# ATMega328_Control_Board.net
KiCad netlist of a schematic drawn in Altium Designer
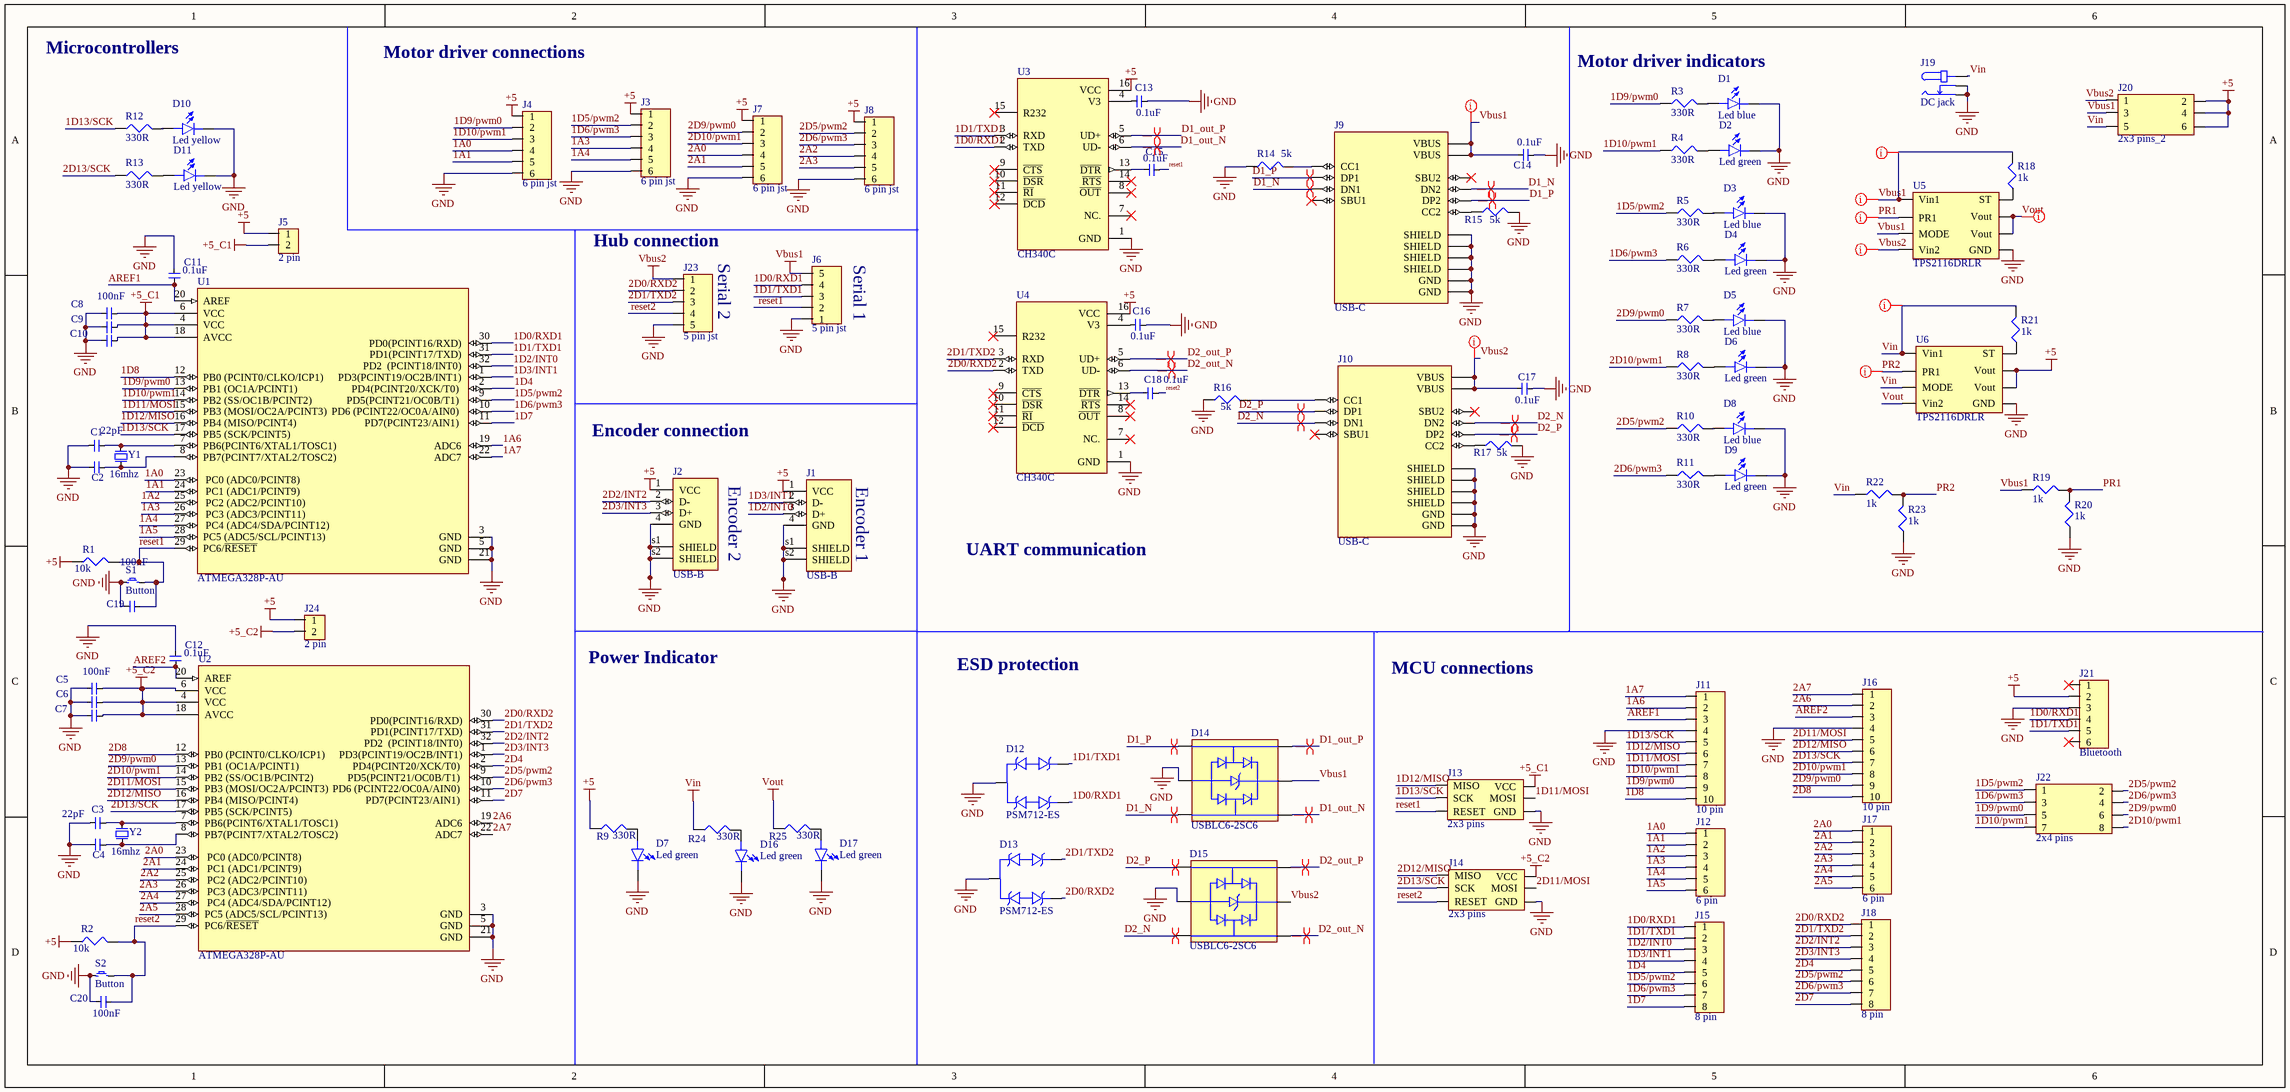
[diagram p0: ATMega328 Control Board.SchDoc]

(export (version "E")
  (design (tool "Eeschema 10.0.6"))
  (components
    (comp (ref "C1")
      (value "22pF")
      (footprint "0603 cap")
      (description "50V 22pF C0G ±5% 0603 Multilayer Ceramic Capacitors MLCC - SMD/SMT ROHS")
      (fields
        (field (name "MANUFACTURER") "PSA(Prosperity Dielectrics)")
        (field (name "MFR. PART #") "FN18N220J500PSG")
      )
      (libsource (lib "Schlib1") (part "22pF capacitor"))
    )
    (comp (ref "C2")
      (value "22pF")
      (footprint "0603 cap")
      (description "50V 22pF C0G ±5% 0603 Multilayer Ceramic Capacitors MLCC - SMD/SMT ROHS")
      (fields
        (field (name "MANUFACTURER") "PSA(Prosperity Dielectrics)")
        (field (name "MFR. PART #") "FN18N220J500PSG")
      )
      (libsource (lib "Schlib1") (part "22pF capacitor"))
    )
    (comp (ref "C3")
      (value "22pF")
      (footprint "0603 cap")
      (description "50V 22pF C0G ±5% 0603 Multilayer Ceramic Capacitors MLCC - SMD/SMT ROHS")
      (fields
        (field (name "MANUFACTURER") "PSA(Prosperity Dielectrics)")
        (field (name "MFR. PART #") "FN18N220J500PSG")
      )
      (libsource (lib "Schlib1") (part "22pF capacitor"))
    )
    (comp (ref "C4")
      (value "22pF")
      (footprint "0603 cap")
      (description "50V 22pF C0G ±5% 0603 Multilayer Ceramic Capacitors MLCC - SMD/SMT ROHS")
      (fields
        (field (name "MANUFACTURER") "PSA(Prosperity Dielectrics)")
        (field (name "MFR. PART #") "FN18N220J500PSG")
      )
      (libsource (lib "Schlib1") (part "22pF capacitor"))
    )
    (comp (ref "C5")
      (value "100nF")
      (footprint "0603 cap")
      (description "50V 100nF X7R ±10% 0603 Multilayer Ceramic Capacitors MLCC - SMD/SMT ROHS")
      (fields
        (field (name "MANUFACTURER") "PSA(Prosperity Dielectrics)")
        (field (name "MFR. PART #") "FN18X104K500PBG")
      )
      (libsource (lib "Schlib1") (part "100nF capacitor"))
    )
    (comp (ref "C6")
      (value "100nF")
      (footprint "0603 cap")
      (description "50V 100nF X7R ±10% 0603 Multilayer Ceramic Capacitors MLCC - SMD/SMT ROHS")
      (fields
        (field (name "MANUFACTURER") "PSA(Prosperity Dielectrics)")
        (field (name "MFR. PART #") "FN18X104K500PBG")
      )
      (libsource (lib "Schlib1") (part "100nF capacitor"))
    )
    (comp (ref "C7")
      (value "100nF")
      (footprint "0603 cap")
      (description "50V 100nF X7R ±10% 0603 Multilayer Ceramic Capacitors MLCC - SMD/SMT ROHS")
      (fields
        (field (name "MANUFACTURER") "PSA(Prosperity Dielectrics)")
        (field (name "MFR. PART #") "FN18X104K500PBG")
      )
      (libsource (lib "Schlib1") (part "100nF capacitor"))
    )
    (comp (ref "C8")
      (value "100nF")
      (footprint "0603 cap")
      (description "50V 100nF X7R ±10% 0603 Multilayer Ceramic Capacitors MLCC - SMD/SMT ROHS")
      (fields
        (field (name "MANUFACTURER") "PSA(Prosperity Dielectrics)")
        (field (name "MFR. PART #") "FN18X104K500PBG")
      )
      (libsource (lib "Schlib1") (part "100nF capacitor"))
    )
    (comp (ref "C9")
      (value "100nF")
      (footprint "0603 cap")
      (description "50V 100nF X7R ±10% 0603 Multilayer Ceramic Capacitors MLCC - SMD/SMT ROHS")
      (fields
        (field (name "MANUFACTURER") "PSA(Prosperity Dielectrics)")
        (field (name "MFR. PART #") "FN18X104K500PBG")
      )
      (libsource (lib "Schlib1") (part "100nF capacitor"))
    )
    (comp (ref "C10")
      (value "100nF")
      (footprint "0603 cap")
      (description "50V 100nF X7R ±10% 0603 Multilayer Ceramic Capacitors MLCC - SMD/SMT ROHS")
      (fields
        (field (name "MANUFACTURER") "PSA(Prosperity Dielectrics)")
        (field (name "MFR. PART #") "FN18X104K500PBG")
      )
      (libsource (lib "Schlib1") (part "100nF capacitor"))
    )
    (comp (ref "C11")
      (value "0.1uF")
      (footprint "0603 cap")
      (description "50V 100nF X7R ±10% 0603 Multilayer Ceramic Capacitors MLCC - SMD/SMT ROHS")
      (fields
        (field (name "MANUFACTURER") "PSA(Prosperity Dielectrics)")
        (field (name "MFR. PART #") "FN18X104K500PBG")
      )
      (libsource (lib "Schlib1") (part "100nF capacitor"))
    )
    (comp (ref "C12")
      (value "0.1uF")
      (footprint "0603 cap")
      (description "50V 100nF X7R ±10% 0603 Multilayer Ceramic Capacitors MLCC - SMD/SMT ROHS")
      (fields
        (field (name "MANUFACTURER") "PSA(Prosperity Dielectrics)")
        (field (name "MFR. PART #") "FN18X104K500PBG")
      )
      (libsource (lib "Schlib1") (part "100nF capacitor"))
    )
    (comp (ref "C13")
      (value "0.1uF")
      (footprint "0603 cap")
      (description "50V 100nF X7R ±10% 0603 Multilayer Ceramic Capacitors MLCC - SMD/SMT ROHS")
      (fields
        (field (name "MANUFACTURER") "PSA(Prosperity Dielectrics)")
        (field (name "MFR. PART #") "FN18X104K500PBG")
      )
      (libsource (lib "Schlib1") (part "100nF capacitor"))
    )
    (comp (ref "C14")
      (value "0.1uF")
      (footprint "0603 cap")
      (description "50V 100nF X7R ±10% 0603 Multilayer Ceramic Capacitors MLCC - SMD/SMT ROHS")
      (fields
        (field (name "MANUFACTURER") "PSA(Prosperity Dielectrics)")
        (field (name "MFR. PART #") "FN18X104K500PBG")
      )
      (libsource (lib "Schlib1") (part "100nF capacitor"))
    )
    (comp (ref "C15")
      (value "0.1uF")
      (footprint "0603 cap")
      (description "50V 100nF X7R ±10% 0603 Multilayer Ceramic Capacitors MLCC - SMD/SMT ROHS")
      (fields
        (field (name "MANUFACTURER") "PSA(Prosperity Dielectrics)")
        (field (name "MFR. PART #") "FN18X104K500PBG")
      )
      (libsource (lib "Schlib1") (part "100nF capacitor"))
    )
    (comp (ref "C16")
      (value "0.1uF")
      (footprint "0603 cap")
      (description "50V 100nF X7R ±10% 0603 Multilayer Ceramic Capacitors MLCC - SMD/SMT ROHS")
      (fields
        (field (name "MANUFACTURER") "PSA(Prosperity Dielectrics)")
        (field (name "MFR. PART #") "FN18X104K500PBG")
      )
      (libsource (lib "Schlib1") (part "100nF capacitor"))
    )
    (comp (ref "C17")
      (value "0.1uF")
      (footprint "0603 cap")
      (description "50V 100nF X7R ±10% 0603 Multilayer Ceramic Capacitors MLCC - SMD/SMT ROHS")
      (fields
        (field (name "MANUFACTURER") "PSA(Prosperity Dielectrics)")
        (field (name "MFR. PART #") "FN18X104K500PBG")
      )
      (libsource (lib "Schlib1") (part "100nF capacitor"))
    )
    (comp (ref "C18")
      (value "0.1uF")
      (footprint "0603 cap")
      (description "50V 100nF X7R ±10% 0603 Multilayer Ceramic Capacitors MLCC - SMD/SMT ROHS")
      (fields
        (field (name "MANUFACTURER") "PSA(Prosperity Dielectrics)")
        (field (name "MFR. PART #") "FN18X104K500PBG")
      )
      (libsource (lib "Schlib1") (part "100nF capacitor"))
    )
    (comp (ref "C19")
      (value "100nF")
      (footprint "0603 cap")
      (description "50V 100nF X7R ±10% 0603 Multilayer Ceramic Capacitors MLCC - SMD/SMT ROHS")
      (fields
        (field (name "MANUFACTURER") "PSA(Prosperity Dielectrics)")
        (field (name "MFR. PART #") "FN18X104K500PBG")
      )
      (libsource (lib "Schlib1") (part "100nF capacitor"))
    )
    (comp (ref "C20")
      (value "100nF")
      (footprint "0603 cap")
      (description "50V 100nF X7R ±10% 0603 Multilayer Ceramic Capacitors MLCC - SMD/SMT ROHS")
      (fields
        (field (name "MANUFACTURER") "PSA(Prosperity Dielectrics)")
        (field (name "MFR. PART #") "FN18X104K500PBG")
      )
      (libsource (lib "Schlib1") (part "100nF capacitor"))
    )
    (comp (ref "D1")
      (value "Led blue")
      (footprint "0805led")
      (description "Blue 0603 Light Emitting Diodes (LED) ROHS")
      (fields (field (name "MANUFACTURER") "Yongyu Photoelectric") (field (name "MFR. PART #") "SZYY0805B"))
      (libsource (lib "Schlib1") (part "Led blue"))
    )
    (comp (ref "D2")
      (value "Led green")
      (footprint "0805led")
      (description "Emerald 0805 Light Emitting Diodes (LED) ROHS")
      (fields (field (name "MANUFACTURER") "Yongyu Photoelectric") (field (name "MFR. PART #") "SZYY0805G"))
      (libsource (lib "Schlib1") (part "Led green"))
    )
    (comp (ref "D3")
      (value "Led blue")
      (footprint "0805led")
      (description "Blue 0603 Light Emitting Diodes (LED) ROHS")
      (fields (field (name "MANUFACTURER") "Yongyu Photoelectric") (field (name "MFR. PART #") "SZYY0805B"))
      (libsource (lib "Schlib1") (part "Led blue"))
    )
    (comp (ref "D4")
      (value "Led green")
      (footprint "0805led")
      (description "Emerald 0805 Light Emitting Diodes (LED) ROHS")
      (fields (field (name "MANUFACTURER") "Yongyu Photoelectric") (field (name "MFR. PART #") "SZYY0805G"))
      (libsource (lib "Schlib1") (part "Led green"))
    )
    (comp (ref "D5")
      (value "Led blue")
      (footprint "0805led")
      (description "Blue 0603 Light Emitting Diodes (LED) ROHS")
      (fields (field (name "MANUFACTURER") "Yongyu Photoelectric") (field (name "MFR. PART #") "SZYY0805B"))
      (libsource (lib "Schlib1") (part "Led blue"))
    )
    (comp (ref "D6")
      (value "Led green")
      (footprint "0805led")
      (description "Emerald 0805 Light Emitting Diodes (LED) ROHS")
      (fields (field (name "MANUFACTURER") "Yongyu Photoelectric") (field (name "MFR. PART #") "SZYY0805G"))
      (libsource (lib "Schlib1") (part "Led green"))
    )
    (comp (ref "D7")
      (value "Led green")
      (footprint "0805led")
      (description "Emerald 0805 Light Emitting Diodes (LED) ROHS")
      (fields (field (name "MANUFACTURER") "Yongyu Photoelectric") (field (name "MFR. PART #") "SZYY0805G"))
      (libsource (lib "Schlib1") (part "Led green"))
    )
    (comp (ref "D8")
      (value "Led blue")
      (footprint "0805led")
      (description "Blue 0603 Light Emitting Diodes (LED) ROHS")
      (fields (field (name "MANUFACTURER") "Yongyu Photoelectric") (field (name "MFR. PART #") "SZYY0805B"))
      (libsource (lib "Schlib1") (part "Led blue"))
    )
    (comp (ref "D9")
      (value "Led green")
      (footprint "0805led")
      (description "Emerald 0805 Light Emitting Diodes (LED) ROHS")
      (fields (field (name "MANUFACTURER") "Yongyu Photoelectric") (field (name "MFR. PART #") "SZYY0805G"))
      (libsource (lib "Schlib1") (part "Led green"))
    )
    (comp (ref "D10")
      (value "Led yellow")
      (footprint "0805led")
      (description "10mA 无色透明透镜 -40℃~+85℃ 584nm~594nm Yellow 120° 40mW 0805 Light Emitting Diodes (LED) ROHS")
      (fields (field (name "MANUFACTURER") "Yongyu Photoelectric") (field (name "MFR. PART #") "SZYY0805Y"))
      (libsource (lib "Schlib1") (part "Led yellow"))
    )
    (comp (ref "D11")
      (value "Led yellow")
      (footprint "0805led")
      (description "10mA 无色透明透镜 -40℃~+85℃ 584nm~594nm Yellow 120° 40mW 0805 Light Emitting Diodes (LED) ROHS")
      (fields (field (name "MANUFACTURER") "Yongyu Photoelectric") (field (name "MFR. PART #") "SZYY0805Y"))
      (libsource (lib "Schlib1") (part "Led yellow"))
    )
    (comp (ref "D12")
      (value "PSM712-ES")
      (footprint "sop23")
      (description "17A 350W Bi-Directional SOT-23 Electrostatic and Surge Protection (TVS/ESD) ROHS")
      (fields (field (name "MANUFACTURER") "ElecSuper") (field (name "LCSC PART #") "C5180294"))
      (libsource (lib "Schlib1") (part "PSM712-ES"))
    )
    (comp (ref "D13")
      (value "PSM712-ES")
      (footprint "sop23")
      (description "17A 350W Bi-Directional SOT-23 Electrostatic and Surge Protection (TVS/ESD) ROHS")
      (fields (field (name "MANUFACTURER") "ElecSuper") (field (name "LCSC PART #") "C5180294"))
      (libsource (lib "Schlib1") (part "PSM712-ES"))
    )
    (comp (ref "D14")
      (value "USBLC6-2SC6")
      (footprint "SOP23-6l")
      (description "5A 17V 6V Unidirectional 5.25V SOT-23-6 Electrostatic and Surge Protection (TVS/ESD) ROHS")
      (fields (field (name "MANUFACTURER") "STMicroelectronics") (field (name "LCSC PART #") "C7519"))
      (libsource (lib "Schlib1") (part "USBLC6-2SC6"))
    )
    (comp (ref "D15")
      (value "USBLC6-2SC6")
      (footprint "SOP23-6l")
      (description "5A 17V 6V Unidirectional 5.25V SOT-23-6 Electrostatic and Surge Protection (TVS/ESD) ROHS")
      (fields (field (name "MANUFACTURER") "STMicroelectronics") (field (name "LCSC PART #") "C7519"))
      (libsource (lib "Schlib1") (part "USBLC6-2SC6"))
    )
    (comp (ref "D16")
      (value "Led green")
      (footprint "0805led")
      (description "Emerald 0805 Light Emitting Diodes (LED) ROHS")
      (fields (field (name "MANUFACTURER") "Yongyu Photoelectric") (field (name "MFR. PART #") "SZYY0805G"))
      (libsource (lib "Schlib1") (part "Led green"))
    )
    (comp (ref "D17")
      (value "Led green")
      (footprint "0805led")
      (description "Emerald 0805 Light Emitting Diodes (LED) ROHS")
      (fields (field (name "MANUFACTURER") "Yongyu Photoelectric") (field (name "MFR. PART #") "SZYY0805G"))
      (libsource (lib "Schlib1") (part "Led green"))
    )
    (comp (ref "J1")
      (value "USB-B")
      (footprint "USB")
      (description "USB 2.0 1 4P Female Type-B Plugin USB Connectors ROHS\r\n ROHS")
      (fields
        (field (name "MANUFACTURER") "Jing Extension of the Electronic Co.")
        (field (name "MFR. PART #") "921-111A1010D10200")
      )
      (libsource (lib "Schlib1") (part "USB-B"))
    )
    (comp (ref "J2")
      (value "USB-B")
      (footprint "USB")
      (description "USB 2.0 1 4P Female Type-B Plugin USB Connectors ROHS\r\n ROHS")
      (fields
        (field (name "MANUFACTURER") "Jing Extension of the Electronic Co.")
        (field (name "MFR. PART #") "921-111A1010D10200")
      )
      (libsource (lib "Schlib1") (part "USB-B"))
    )
    (comp (ref "J3")
      (value "6 pin jst")
      (footprint "6 jst")
      (description "1x6P 6P XH 1 2.5mm 6 Plugin,P=2.5mm Wire To Board Connector ROHS")
      (fields (field (name "MANUFACTURER") "BOOMELE") (field (name "MFR. PART #") "XH-6A"))
      (libsource (lib "Schlib1") (part "6 pin jst"))
    )
    (comp (ref "J4")
      (value "6 pin jst")
      (footprint "6 jst")
      (description "1x6P 6P XH 1 2.5mm 6 Plugin,P=2.5mm Wire To Board Connector ROHS")
      (fields (field (name "MANUFACTURER") "BOOMELE") (field (name "MFR. PART #") "XH-6A"))
      (libsource (lib "Schlib1") (part "6 pin jst"))
    )
    (comp (ref "J5")
      (value "2 pin")
      (footprint "2 pin header")
      (fields
        (field (name "MANUFACTURER") "XUNPU")
        (field (name "MFR. PART #") "PH2.54-01-02PZD")
        (field (name "LCSC PART #") "C7501580")
      )
      (libsource (lib "Schlib1") (part "2 pin"))
    )
    (comp (ref "J6")
      (value "5 pin jst")
      (footprint "5 jst")
      (description "1x5P 5P XH 1 2.5mm 6 Plugin,P=2.5mm Wire To Board Connector ROHS")
      (fields (field (name "MANUFACTURER") "BOOMELE") (field (name "MFR. PART #") "XH-6A"))
      (libsource (lib "") (part "5 pin jst_1"))
    )
    (comp (ref "J7")
      (value "6 pin jst")
      (footprint "6 jst")
      (description "1x6P 6P XH 1 2.5mm 6 Plugin,P=2.5mm Wire To Board Connector ROHS")
      (fields (field (name "MANUFACTURER") "BOOMELE") (field (name "MFR. PART #") "XH-6A"))
      (libsource (lib "Schlib1") (part "6 pin jst"))
    )
    (comp (ref "J8")
      (value "6 pin jst")
      (footprint "6 jst")
      (description "1x6P 6P XH 1 2.5mm 6 Plugin,P=2.5mm Wire To Board Connector ROHS")
      (fields (field (name "MANUFACTURER") "BOOMELE") (field (name "MFR. PART #") "XH-6A"))
      (libsource (lib "Schlib1") (part "6 pin jst"))
    )
    (comp (ref "J9")
      (value "USB-C")
      (footprint "USB-C")
      (description "5A 1 16P Female Type-C SMD USB Connectors ROHS")
      (fields
        (field (name "MANUFACTURER") "Korean Hroparts Elec")
        (field (name "MFR. PART #") "TYPE-C-31-M-12")
      )
      (libsource (lib "Schlib1") (part "USB-C"))
    )
    (comp (ref "J10")
      (value "USB-C")
      (footprint "USB-C")
      (description "5A 1 16P Female Type-C SMD USB Connectors ROHS")
      (fields
        (field (name "MANUFACTURER") "Korean Hroparts Elec")
        (field (name "MFR. PART #") "TYPE-C-31-M-12")
      )
      (libsource (lib "Schlib1") (part "USB-C"))
    )
    (comp (ref "J11")
      (value "10 pin")
      (footprint "10 pin header")
      (fields
        (field (name "MANUFACTURER") "Shenzhen Kinghelm Elec")
        (field (name "MFR. PART #") "KH-2.54FH-1X10P-H8.5")
        (field (name "LCSC PART #") "C2905418")
      )
      (libsource (lib "Schlib1") (part "10 pin"))
    )
    (comp (ref "J12")
      (value "6 pin")
      (footprint "6 pin header")
      (description "2.54mm Plugin 6P Straight 1x6P Plugin,P=2.54mm Female Headers ROHS")
      (fields (field (name "MANUFACTURER") "BOOMELE") (field (name "MFR. PART #") "2.54-1*6P"))
      (libsource (lib "Schlib1") (part "6 pin"))
    )
    (comp (ref "J13")
      (value "2x3 pins")
      (footprint "2x3 pins")
      (description "Straight 2.54mm 6mm 6P 3mm 2.54mm 双排 2x3P Plugin,P=2.54mm Pin Headers ROHS")
      (fields (field (name "MANUFACTURER") "HanElectricity") (field (name "MFR. PART #") "2541WV-2x03P"))
      (libsource (lib "Schlib1") (part "2x3 pins"))
    )
    (comp (ref "J14")
      (value "2x3 pins")
      (footprint "2x3 pins")
      (description "Straight 2.54mm 6mm 6P 3mm 2.54mm 双排 2x3P Plugin,P=2.54mm Pin Headers ROHS")
      (fields (field (name "MANUFACTURER") "HanElectricity") (field (name "MFR. PART #") "2541WV-2x03P"))
      (libsource (lib "Schlib1") (part "2x3 pins"))
    )
    (comp (ref "J15")
      (value "8 pin")
      (footprint "8 pin heade")
      (description "2.54mm Plugin 8P Straight 1x8P Plugin,P=2.54mm Female Headers ROHS")
      (fields (field (name "MANUFACTURER") "BOOMELE") (field (name "MFR. PART #") "2.54-1*8P"))
      (libsource (lib "Schlib1") (part "8 pin"))
    )
    (comp (ref "J16")
      (value "10 pin")
      (footprint "10 pin header")
      (fields
        (field (name "MANUFACTURER") "Shenzhen Kinghelm Elec")
        (field (name "MFR. PART #") "KH-2.54FH-1X10P-H8.5")
        (field (name "LCSC PART #") "C2905418")
      )
      (libsource (lib "Schlib1") (part "10 pin"))
    )
    (comp (ref "J17")
      (value "6 pin")
      (footprint "6 pin header")
      (description "2.54mm Plugin 6P Straight 1x6P Plugin,P=2.54mm Female Headers ROHS")
      (fields (field (name "MANUFACTURER") "BOOMELE") (field (name "MFR. PART #") "2.54-1*6P"))
      (libsource (lib "Schlib1") (part "6 pin"))
    )
    (comp (ref "J18")
      (value "8 pin")
      (footprint "8 pin heade")
      (description "2.54mm Plugin 8P Straight 1x8P Plugin,P=2.54mm Female Headers ROHS")
      (fields (field (name "MANUFACTURER") "BOOMELE") (field (name "MFR. PART #") "2.54-1*8P"))
      (libsource (lib "Schlib1") (part "8 pin"))
    )
    (comp (ref "J19")
      (value "DC jack")
      (footprint "DC jack")
      (fields
        (field (name "MANUFACTURER") "XKB Connection")
        (field (name "MFR. PART #") "DC-005-2.5A-2.0")
        (field (name "LCSC PART #") "C319099")
      )
      (libsource (lib "Schlib1") (part "DC jack"))
    )
    (comp (ref "J20")
      (value "2x3 pins_2")
      (footprint "2x3 pins")
      (description "Straight 2.54mm 6mm 6P 3mm 2.54mm 双排 2x3P Plugin,P=2.54mm Pin Headers ROHS")
      (fields (field (name "MANUFACTURER") "HanElectricity") (field (name "MFR. PART #") "2541WV-2x03P"))
      (libsource (lib "Schlib1") (part "2x3 pins_2"))
    )
    (comp (ref "J21")
      (value "Bluetooth")
      (footprint "6 pin header")
      (description "2.54mm Plugin 6P Straight 1x6P Plugin,P=2.54mm Female Headers ROHS")
      (fields (field (name "MANUFACTURER") "BOOMELE") (field (name "MFR. PART #") "2.54-1*6P"))
      (libsource (lib "Schlib1") (part "6 pin"))
    )
    (comp (ref "J22")
      (value "2x4 pins")
      (footprint "2x4 pins")
      (fields
        (field (name "MANUFACTURER") "Liansheng")
        (field (name "MFR. PART #") "PH-00179")
        (field (name "LCSC PART #") "C2829882")
      )
      (libsource (lib "Schlib1") (part "2x4 pins"))
    )
    (comp (ref "J23")
      (value "5 pin jst")
      (footprint "5 jst")
      (description "1x5P 5P XH 1 2.5mm 6 Plugin,P=2.5mm Wire To Board Connector ROHS")
      (fields (field (name "MANUFACTURER") "BOOMELE") (field (name "MFR. PART #") "XH-6A"))
      (libsource (lib "Schlib1") (part "5 pin jst"))
    )
    (comp (ref "J24")
      (value "2 pin")
      (footprint "2 pin header")
      (fields
        (field (name "MANUFACTURER") "XUNPU")
        (field (name "MFR. PART #") "PH2.54-01-02PZD")
        (field (name "LCSC PART #") "C7501580")
      )
      (libsource (lib "Schlib1") (part "2 pin"))
    )
    (comp (ref "R1")
      (value "10k")
      (footprint "0603 cap")
      (description "100mW Thick Film Resistors 75V ±100ppm/℃ ±1% 10kΩ 0603 Chip Resistor - Surface Mount ROHS")
      (fields
        (field (name "MANUFACTURER") "UNI-ROYAL(Uniroyal Elec)")
        (field (name "MFR. PART #") "0603WAF1002T5E")
      )
      (libsource (lib "Schlib1") (part "10k resistor"))
    )
    (comp (ref "R2")
      (value "10k")
      (footprint "0603 cap")
      (description "100mW Thick Film Resistors 75V ±100ppm/℃ ±1% 10kΩ 0603 Chip Resistor - Surface Mount ROHS")
      (fields
        (field (name "MANUFACTURER") "UNI-ROYAL(Uniroyal Elec)")
        (field (name "MFR. PART #") "0603WAF1002T5E")
      )
      (libsource (lib "Schlib1") (part "10k resistor"))
    )
    (comp (ref "R3")
      (value "330R")
      (footprint "0603 cap")
      (description "100mW Thick Film Resistors 75V ±100ppm/℃ ±1% 330Ω 0603 Chip Resistor - Surface Mount ROHS")
      (fields
        (field (name "MANUFACTURER") "UNI-ROYAL(Uniroyal Elec)")
        (field (name "MFR. PART #") "0603WAF3300T5E")
      )
      (libsource (lib "Schlib1") (part "330R"))
    )
    (comp (ref "R4")
      (value "330R")
      (footprint "0603 cap")
      (description "100mW Thick Film Resistors 75V ±100ppm/℃ ±1% 330Ω 0603 Chip Resistor - Surface Mount ROHS")
      (fields
        (field (name "MANUFACTURER") "UNI-ROYAL(Uniroyal Elec)")
        (field (name "MFR. PART #") "0603WAF3300T5E")
      )
      (libsource (lib "Schlib1") (part "330R"))
    )
    (comp (ref "R5")
      (value "330R")
      (footprint "0603 cap")
      (description "100mW Thick Film Resistors 75V ±100ppm/℃ ±1% 330Ω 0603 Chip Resistor - Surface Mount ROHS")
      (fields
        (field (name "MANUFACTURER") "UNI-ROYAL(Uniroyal Elec)")
        (field (name "MFR. PART #") "0603WAF3300T5E")
      )
      (libsource (lib "Schlib1") (part "330R"))
    )
    (comp (ref "R6")
      (value "330R")
      (footprint "0603 cap")
      (description "100mW Thick Film Resistors 75V ±100ppm/℃ ±1% 330Ω 0603 Chip Resistor - Surface Mount ROHS")
      (fields
        (field (name "MANUFACTURER") "UNI-ROYAL(Uniroyal Elec)")
        (field (name "MFR. PART #") "0603WAF3300T5E")
      )
      (libsource (lib "Schlib1") (part "330R"))
    )
    (comp (ref "R7")
      (value "330R")
      (footprint "0603 cap")
      (description "100mW Thick Film Resistors 75V ±100ppm/℃ ±1% 330Ω 0603 Chip Resistor - Surface Mount ROHS")
      (fields
        (field (name "MANUFACTURER") "UNI-ROYAL(Uniroyal Elec)")
        (field (name "MFR. PART #") "0603WAF3300T5E")
      )
      (libsource (lib "Schlib1") (part "330R"))
    )
    (comp (ref "R8")
      (value "330R")
      (footprint "0603 cap")
      (description "100mW Thick Film Resistors 75V ±100ppm/℃ ±1% 330Ω 0603 Chip Resistor - Surface Mount ROHS")
      (fields
        (field (name "MANUFACTURER") "UNI-ROYAL(Uniroyal Elec)")
        (field (name "MFR. PART #") "0603WAF3300T5E")
      )
      (libsource (lib "Schlib1") (part "330R"))
    )
    (comp (ref "R9")
      (value "330R")
      (footprint "0603 cap")
      (description "100mW Thick Film Resistors 75V ±100ppm/℃ ±1% 330Ω 0603 Chip Resistor - Surface Mount ROHS")
      (fields
        (field (name "MANUFACTURER") "UNI-ROYAL(Uniroyal Elec)")
        (field (name "MFR. PART #") "0603WAF3300T5E")
      )
      (libsource (lib "Schlib1") (part "330R"))
    )
    (comp (ref "R10")
      (value "330R")
      (footprint "0603 cap")
      (description "100mW Thick Film Resistors 75V ±100ppm/℃ ±1% 330Ω 0603 Chip Resistor - Surface Mount ROHS")
      (fields
        (field (name "MANUFACTURER") "UNI-ROYAL(Uniroyal Elec)")
        (field (name "MFR. PART #") "0603WAF3300T5E")
      )
      (libsource (lib "Schlib1") (part "330R"))
    )
    (comp (ref "R11")
      (value "330R")
      (footprint "0603 cap")
      (description "100mW Thick Film Resistors 75V ±100ppm/℃ ±1% 330Ω 0603 Chip Resistor - Surface Mount ROHS")
      (fields
        (field (name "MANUFACTURER") "UNI-ROYAL(Uniroyal Elec)")
        (field (name "MFR. PART #") "0603WAF3300T5E")
      )
      (libsource (lib "Schlib1") (part "330R"))
    )
    (comp (ref "R12")
      (value "330R")
      (footprint "0603 cap")
      (description "100mW Thick Film Resistors 75V ±100ppm/℃ ±1% 330Ω 0603 Chip Resistor - Surface Mount ROHS")
      (fields
        (field (name "MANUFACTURER") "UNI-ROYAL(Uniroyal Elec)")
        (field (name "MFR. PART #") "0603WAF3300T5E")
      )
      (libsource (lib "Schlib1") (part "330R"))
    )
    (comp (ref "R13")
      (value "330R")
      (footprint "0603 cap")
      (description "100mW Thick Film Resistors 75V ±100ppm/℃ ±1% 330Ω 0603 Chip Resistor - Surface Mount ROHS")
      (fields
        (field (name "MANUFACTURER") "UNI-ROYAL(Uniroyal Elec)")
        (field (name "MFR. PART #") "0603WAF3300T5E")
      )
      (libsource (lib "Schlib1") (part "330R"))
    )
    (comp (ref "R14")
      (value "5k")
      (footprint "0603 cap")
      (description "100mW Thick Film Resistors 75V ±100ppm/℃ ±1% 330Ω 0603 Chip Resistor - Surface Mount ROHS")
      (fields
        (field (name "MANUFACTURER") "UNI-ROYAL(Uniroyal Elec)")
        (field (name "MFR. PART #") "0603WAF5101T5E")
      )
      (libsource (lib "Schlib1") (part "5k"))
    )
    (comp (ref "R15")
      (value "5k")
      (footprint "0603 cap")
      (description "100mW Thick Film Resistors 75V ±100ppm/℃ ±1% 330Ω 0603 Chip Resistor - Surface Mount ROHS")
      (fields
        (field (name "MANUFACTURER") "UNI-ROYAL(Uniroyal Elec)")
        (field (name "MFR. PART #") "0603WAF5101T5E")
      )
      (libsource (lib "Schlib1") (part "5k"))
    )
    (comp (ref "R16")
      (value "5k")
      (footprint "0603 cap")
      (description "100mW Thick Film Resistors 75V ±100ppm/℃ ±1% 330Ω 0603 Chip Resistor - Surface Mount ROHS")
      (fields
        (field (name "MANUFACTURER") "UNI-ROYAL(Uniroyal Elec)")
        (field (name "MFR. PART #") "0603WAF5101T5E")
      )
      (libsource (lib "Schlib1") (part "5k"))
    )
    (comp (ref "R17")
      (value "5k")
      (footprint "0603 cap")
      (description "100mW Thick Film Resistors 75V ±100ppm/℃ ±1% 330Ω 0603 Chip Resistor - Surface Mount ROHS")
      (fields
        (field (name "MANUFACTURER") "UNI-ROYAL(Uniroyal Elec)")
        (field (name "MFR. PART #") "0603WAF5101T5E")
      )
      (libsource (lib "Schlib1") (part "5k"))
    )
    (comp (ref "R18")
      (value "1k")
      (footprint "0603 cap")
      (description "100mW Thick Film Resistors 75V ±100ppm/℃ ±1% 1kΩ 0603 Chip Resistor - Surface Mount ROHS")
      (fields
        (field (name "MANUFACTURER") "UNI-ROYAL(Uniroyal Elec)")
        (field (name "MFR. PART #") "0603WAF1001T5E")
      )
      (libsource (lib "Schlib1") (part "1k resistor"))
    )
    (comp (ref "R19")
      (value "1k")
      (footprint "0603 cap")
      (description "100mW Thick Film Resistors 75V ±100ppm/℃ ±1% 1kΩ 0603 Chip Resistor - Surface Mount ROHS")
      (fields
        (field (name "MANUFACTURER") "UNI-ROYAL(Uniroyal Elec)")
        (field (name "MFR. PART #") "0603WAF1001T5E")
      )
      (libsource (lib "Schlib1") (part "1k resistor"))
    )
    (comp (ref "R20")
      (value "1k")
      (footprint "0603 cap")
      (description "100mW Thick Film Resistors 75V ±100ppm/℃ ±1% 1kΩ 0603 Chip Resistor - Surface Mount ROHS")
      (fields
        (field (name "MANUFACTURER") "UNI-ROYAL(Uniroyal Elec)")
        (field (name "MFR. PART #") "0603WAF1001T5E")
      )
      (libsource (lib "Schlib1") (part "1k resistor"))
    )
    (comp (ref "R21")
      (value "1k")
      (footprint "0603 cap")
      (description "100mW Thick Film Resistors 75V ±100ppm/℃ ±1% 1kΩ 0603 Chip Resistor - Surface Mount ROHS")
      (fields
        (field (name "MANUFACTURER") "UNI-ROYAL(Uniroyal Elec)")
        (field (name "MFR. PART #") "0603WAF1001T5E")
      )
      (libsource (lib "Schlib1") (part "1k resistor"))
    )
    (comp (ref "R22")
      (value "1k")
      (footprint "0603 cap")
      (description "100mW Thick Film Resistors 75V ±100ppm/℃ ±1% 1kΩ 0603 Chip Resistor - Surface Mount ROHS")
      (fields
        (field (name "MANUFACTURER") "UNI-ROYAL(Uniroyal Elec)")
        (field (name "MFR. PART #") "0603WAF1001T5E")
      )
      (libsource (lib "Schlib1") (part "1k resistor"))
    )
    (comp (ref "R23")
      (value "1k")
      (footprint "0603 cap")
      (description "100mW Thick Film Resistors 75V ±100ppm/℃ ±1% 1kΩ 0603 Chip Resistor - Surface Mount ROHS")
      (fields
        (field (name "MANUFACTURER") "UNI-ROYAL(Uniroyal Elec)")
        (field (name "MFR. PART #") "0603WAF1001T5E")
      )
      (libsource (lib "Schlib1") (part "1k resistor"))
    )
    (comp (ref "R24")
      (value "330R")
      (footprint "0603 cap")
      (description "100mW Thick Film Resistors 75V ±100ppm/℃ ±1% 330Ω 0603 Chip Resistor - Surface Mount ROHS")
      (fields
        (field (name "MANUFACTURER") "UNI-ROYAL(Uniroyal Elec)")
        (field (name "MFR. PART #") "0603WAF3300T5E")
      )
      (libsource (lib "Schlib1") (part "330R"))
    )
    (comp (ref "R25")
      (value "330R")
      (footprint "0603 cap")
      (description "100mW Thick Film Resistors 75V ±100ppm/℃ ±1% 330Ω 0603 Chip Resistor - Surface Mount ROHS")
      (fields
        (field (name "MANUFACTURER") "UNI-ROYAL(Uniroyal Elec)")
        (field (name "MFR. PART #") "0603WAF3300T5E")
      )
      (libsource (lib "Schlib1") (part "330R"))
    )
    (comp (ref "S1")
      (value "Button")
      (footprint "button")
      (fields
        (field (name "MANUFACTURER") "USAKRO")
        (field (name "MFR. PART #") "UK-B0240-R-250")
        (field (name "LCSC PART #") "C556660")
      )
      (libsource (lib "Schlib1") (part "tactile button"))
    )
    (comp (ref "S2")
      (value "Button")
      (footprint "button")
      (fields
        (field (name "MANUFACTURER") "USAKRO")
        (field (name "MFR. PART #") "UK-B0240-R-250")
        (field (name "LCSC PART #") "C556660")
      )
      (libsource (lib "Schlib1") (part "tactile button"))
    )
    (comp (ref "U1")
      (value "ATMEGA328P-AU")
      (footprint "Quad32")
      (description "32KB 2KB FLASH 23 1.8V~5.5V AVR 20MHz TQFP-32(7x7) Microcontroller Units (MCUs/MPUs/SOCs) ROHS")
      (fields (field (name "MANUFACTURER") "Microchip Tech") (field (name "LCSC PART #") "C14877"))
      (libsource (lib "Schlib1") (part "ATMEGA328P-AU"))
    )
    (comp (ref "U2")
      (value "ATMEGA328P-AU")
      (footprint "Quad32")
      (description "32KB 2KB FLASH 23 1.8V~5.5V AVR 20MHz TQFP-32(7x7) Microcontroller Units (MCUs/MPUs/SOCs) ROHS")
      (fields (field (name "MANUFACTURER") "Microchip Tech") (field (name "LCSC PART #") "C14877"))
      (libsource (lib "Schlib1") (part "ATMEGA328P-AU"))
    )
    (comp (ref "U3")
      (value "CH340C")
      (footprint "sop 16")
      (description "2Mbps Transceiver USB 2.0 SOP-16 USB ICs ROHS")
      (fields (field (name "MANUFACTURER") "WCH") (field (name "LCSC PART #") "C84681"))
      (libsource (lib "Schlib1") (part "CH340C"))
    )
    (comp (ref "U4")
      (value "CH340C")
      (footprint "sop 16")
      (description "2Mbps Transceiver USB 2.0 SOP-16 USB ICs ROHS")
      (fields (field (name "MANUFACTURER") "WCH") (field (name "LCSC PART #") "C84681"))
      (libsource (lib "Schlib1") (part "CH340C"))
    )
    (comp (ref "U5")
      (value "TPS2116DRLR")
      (footprint "SOP8")
      (description "1.6V~5.5V 42mΩ 2.5A 1 SOT-583 Power Distribution Switches ROHS")
      (fields (field (name "MANUFACTURER") "Texas Instruments") (field (name "LCSC PART #") "C3235557"))
      (libsource (lib "Schlib1") (part "TPS2116DRLR"))
    )
    (comp (ref "U6")
      (value "TPS2116DRLR")
      (footprint "SOP8")
      (description "1.6V~5.5V 42mΩ 2.5A 1 SOT-583 Power Distribution Switches ROHS")
      (fields (field (name "MANUFACTURER") "Texas Instruments") (field (name "LCSC PART #") "C3235557"))
      (libsource (lib "Schlib1") (part "TPS2116DRLR"))
    )
    (comp (ref "Y1")
      (value "16mhz")
      (footprint "crystal")
      (description "16MHz 16pF ±20ppm ±20ppm HC-49S-SMD Crystals ROHS")
      (fields (field (name "MANUFACTURER") "KYX") (field (name "MFR. PART #") "KBD160001620"))
      (libsource (lib "Schlib1") (part "Crystal 16mhz"))
    )
    (comp (ref "Y2")
      (value "16mhz")
      (footprint "crystal")
      (description "16MHz 16pF ±20ppm ±20ppm HC-49S-SMD Crystals ROHS")
      (fields (field (name "MANUFACTURER") "KYX") (field (name "MFR. PART #") "KBD160001620"))
      (libsource (lib "Schlib1") (part "Crystal 16mhz"))
    )
  )
  (nets
    (net (code "1") (name "+5") (class "Default")
      (node (ref "J1") (pin "1") (pinfunction "VCC_1") (pintype "power_in"))
      (node (ref "J2") (pin "1") (pinfunction "VCC_1") (pintype "power_in"))
      (node (ref "J20") (pin "2") (pinfunction "2_2") (pintype "passive"))
      (node (ref "J20") (pin "4") (pinfunction "4_4") (pintype "passive"))
      (node (ref "J20") (pin "6") (pinfunction "6_6") (pintype "passive"))
      (node (ref "J21") (pin "2") (pinfunction "2_2") (pintype "passive"))
      (node (ref "J24") (pin "1") (pinfunction "1_1") (pintype "passive"))
      (node (ref "J3") (pin "1") (pinfunction "1_1") (pintype "passive"))
      (node (ref "J4") (pin "1") (pinfunction "1_1") (pintype "passive"))
      (node (ref "J5") (pin "1") (pinfunction "1_1") (pintype "passive"))
      (node (ref "J7") (pin "1") (pinfunction "1_1") (pintype "passive"))
      (node (ref "J8") (pin "1") (pinfunction "1_1") (pintype "passive"))
      (node (ref "R1") (pin "1") (pinfunction "1_1") (pintype "passive"))
      (node (ref "R2") (pin "1") (pinfunction "1_1") (pintype "passive"))
      (node (ref "R9") (pin "1") (pinfunction "1_1") (pintype "passive"))
      (node (ref "U3") (pin "16") (pinfunction "VCC_16") (pintype "power_in"))
      (node (ref "U4") (pin "16") (pinfunction "VCC_16") (pintype "power_in"))
      (node (ref "U6") (pin "2") (pinfunction "Vout_2") (pintype "passive"))
      (node (ref "U6") (pin "7") (pinfunction "Vout_7") (pintype "passive"))
    )
    (net (code "2") (name "+5_C1") (class "Default")
      (node (ref "C10") (pin "2") (pinfunction "2_2") (pintype "passive"))
      (node (ref "C8") (pin "2") (pinfunction "2_2") (pintype "passive"))
      (node (ref "C9") (pin "2") (pinfunction "2_2") (pintype "passive"))
      (node (ref "J13") (pin "2") (pinfunction "VCC_2") (pintype "passive"))
      (node (ref "J5") (pin "2") (pinfunction "2_2") (pintype "passive"))
      (node (ref "U1") (pin "18") (pinfunction "AVCC_18") (pintype "power_in"))
      (node (ref "U1") (pin "4") (pinfunction "VCC_4") (pintype "power_in"))
      (node (ref "U1") (pin "6") (pinfunction "VCC_6") (pintype "power_in"))
    )
    (net (code "3") (name "+5_C2") (class "Default")
      (node (ref "C5") (pin "2") (pinfunction "2_2") (pintype "passive"))
      (node (ref "C6") (pin "2") (pinfunction "2_2") (pintype "passive"))
      (node (ref "C7") (pin "2") (pinfunction "2_2") (pintype "passive"))
      (node (ref "J14") (pin "2") (pinfunction "VCC_2") (pintype "passive"))
      (node (ref "J24") (pin "2") (pinfunction "2_2") (pintype "passive"))
      (node (ref "U2") (pin "18") (pinfunction "AVCC_18") (pintype "power_in"))
      (node (ref "U2") (pin "4") (pinfunction "VCC_4") (pintype "power_in"))
      (node (ref "U2") (pin "6") (pinfunction "VCC_6") (pintype "power_in"))
    )
    (net (code "4") (name "/1A0") (class "Default")
      (node (ref "J12") (pin "1") (pinfunction "1_1") (pintype "passive"))
      (node (ref "J4") (pin "4") (pinfunction "4_4") (pintype "passive"))
      (node (ref "U1") (pin "23") (pinfunction "_PC0_(ADC0/PCINT8)_23") (pintype "bidirectional"))
    )
    (net (code "5") (name "/1A1") (class "Default")
      (node (ref "J12") (pin "2") (pinfunction "2_2") (pintype "passive"))
      (node (ref "J4") (pin "5") (pinfunction "5_5") (pintype "passive"))
      (node (ref "U1") (pin "24") (pinfunction "_PC1_(ADC1/PCINT9)_24") (pintype "bidirectional"))
    )
    (net (code "6") (name "/1A2") (class "Default")
      (node (ref "J12") (pin "3") (pinfunction "3_3") (pintype "passive"))
      (node (ref "U1") (pin "25") (pinfunction "_PC2_(ADC2/PCINT10)_25") (pintype "bidirectional"))
    )
    (net (code "7") (name "/1A3") (class "Default")
      (node (ref "J12") (pin "4") (pinfunction "4_4") (pintype "passive"))
      (node (ref "J3") (pin "4") (pinfunction "4_4") (pintype "passive"))
      (node (ref "U1") (pin "26") (pinfunction "_PC3_(ADC3/PCINT11)_26") (pintype "bidirectional"))
    )
    (net (code "8") (name "/1A4") (class "Default")
      (node (ref "J12") (pin "5") (pinfunction "5_5") (pintype "passive"))
      (node (ref "J3") (pin "5") (pinfunction "5_5") (pintype "passive"))
      (node (ref "U1") (pin "27") (pinfunction "_PC4_(ADC4/SDA/PCINT12)_27") (pintype "bidirectional"))
    )
    (net (code "9") (name "/1A5") (class "Default")
      (node (ref "J12") (pin "6") (pinfunction "6_6") (pintype "passive"))
      (node (ref "U1") (pin "28") (pinfunction "PC5_(ADC5/SCL/PCINT13)_28") (pintype "bidirectional"))
    )
    (net (code "10") (name "/1A6") (class "Default")
      (node (ref "J11") (pin "2") (pinfunction "2_2") (pintype "passive"))
      (node (ref "U1") (pin "19") (pinfunction "ADC6_19") (pintype "bidirectional"))
    )
    (net (code "11") (name "/1A7") (class "Default")
      (node (ref "J11") (pin "1") (pinfunction "1_1") (pintype "passive"))
      (node (ref "U1") (pin "22") (pinfunction "ADC7_22") (pintype "bidirectional"))
    )
    (net (code "12") (name "/1D0{slash}RXD1") (class "Default")
      (node (ref "D12") (pin "1") (pinfunction "1_1") (pintype "passive"))
      (node (ref "J15") (pin "1") (pinfunction "1_1") (pintype "passive"))
      (node (ref "J21") (pin "4") (pinfunction "4_4") (pintype "passive"))
      (node (ref "J6") (pin "4") (pinfunction "4_4") (pintype "passive"))
      (node (ref "U1") (pin "30") (pinfunction "PD0(PCINT16/RXD)_30") (pintype "bidirectional"))
      (node (ref "U3") (pin "2") (pinfunction "TXD_2") (pintype "bidirectional"))
    )
    (net (code "13") (name "/1D1{slash}TXD1") (class "Default")
      (node (ref "D12") (pin "2") (pinfunction "2_2") (pintype "passive"))
      (node (ref "J15") (pin "2") (pinfunction "2_2") (pintype "passive"))
      (node (ref "J21") (pin "5") (pinfunction "5_5") (pintype "passive"))
      (node (ref "J6") (pin "3") (pinfunction "3_3") (pintype "passive"))
      (node (ref "U1") (pin "31") (pinfunction "PD1(PCINT17/TXD)_31") (pintype "bidirectional"))
      (node (ref "U3") (pin "3") (pinfunction "RXD_3") (pintype "bidirectional"))
    )
    (net (code "14") (name "/1D2{slash}INT0") (class "Default")
      (node (ref "J1") (pin "3") (pinfunction "D+_3") (pintype "bidirectional"))
      (node (ref "J15") (pin "3") (pinfunction "3_3") (pintype "passive"))
      (node (ref "U1") (pin "32") (pinfunction "PD2__(PCINT18/INT0)_32") (pintype "bidirectional"))
    )
    (net (code "15") (name "/1D3{slash}INT1") (class "Default")
      (node (ref "J1") (pin "2") (pinfunction "D-_2") (pintype "bidirectional"))
      (node (ref "J15") (pin "4") (pinfunction "4_4") (pintype "passive"))
      (node (ref "U1") (pin "1") (pinfunction "PD3(PCINT19/OC2B/INT1)_1") (pintype "bidirectional"))
    )
    (net (code "16") (name "/1D4") (class "Default")
      (node (ref "J15") (pin "5") (pinfunction "5_5") (pintype "passive"))
      (node (ref "U1") (pin "2") (pinfunction "PD4(PCINT20/XCK/T0)_2") (pintype "bidirectional"))
    )
    (net (code "17") (name "/1D5{slash}pwm2") (class "Default")
      (node (ref "J15") (pin "6") (pinfunction "6_6") (pintype "passive"))
      (node (ref "J22") (pin "1") (pinfunction "1_1") (pintype "passive"))
      (node (ref "J3") (pin "2") (pinfunction "2_2") (pintype "passive"))
      (node (ref "R5") (pin "1") (pinfunction "1_1") (pintype "passive"))
      (node (ref "U1") (pin "9") (pinfunction "PD5(PCINT21/OC0B/T1)_9") (pintype "bidirectional"))
    )
    (net (code "18") (name "/1D6{slash}pwm3") (class "Default")
      (node (ref "J15") (pin "7") (pinfunction "7_7") (pintype "passive"))
      (node (ref "J22") (pin "3") (pinfunction "3_3") (pintype "passive"))
      (node (ref "J3") (pin "3") (pinfunction "3_3") (pintype "passive"))
      (node (ref "R6") (pin "1") (pinfunction "1_1") (pintype "passive"))
      (node (ref "U1") (pin "10") (pinfunction "PD6_(PCINT22/OC0A/AIN0)_10") (pintype "bidirectional"))
    )
    (net (code "19") (name "/1D7") (class "Default")
      (node (ref "J15") (pin "8") (pinfunction "8_8") (pintype "passive"))
      (node (ref "U1") (pin "11") (pinfunction "PD7(PCINT23/AIN1)_11") (pintype "bidirectional"))
    )
    (net (code "20") (name "/1D8") (class "Default")
      (node (ref "J11") (pin "10") (pinfunction "10_10") (pintype "passive"))
      (node (ref "U1") (pin "12") (pinfunction "PB0_(PCINT0/CLKO/ICP1)_12") (pintype "bidirectional"))
    )
    (net (code "21") (name "/1D9{slash}pwm0") (class "Default")
      (node (ref "J11") (pin "9") (pinfunction "9_9") (pintype "passive"))
      (node (ref "J22") (pin "5") (pinfunction "5_5") (pintype "passive"))
      (node (ref "J4") (pin "2") (pinfunction "2_2") (pintype "passive"))
      (node (ref "R3") (pin "1") (pinfunction "1_1") (pintype "passive"))
      (node (ref "U1") (pin "13") (pinfunction "PB1_(OC1A/PCINT1)_13") (pintype "bidirectional"))
    )
    (net (code "22") (name "/1D10{slash}pwm1") (class "Default")
      (node (ref "J11") (pin "8") (pinfunction "8_8") (pintype "passive"))
      (node (ref "J22") (pin "7") (pinfunction "7_7") (pintype "passive"))
      (node (ref "J4") (pin "3") (pinfunction "3_3") (pintype "passive"))
      (node (ref "R4") (pin "1") (pinfunction "1_1") (pintype "passive"))
      (node (ref "U1") (pin "14") (pinfunction "PB2_(SS/OC1B/PCINT2)_14") (pintype "bidirectional"))
    )
    (net (code "23") (name "/1D11{slash}MOSI") (class "Default")
      (node (ref "J11") (pin "7") (pinfunction "7_7") (pintype "passive"))
      (node (ref "J13") (pin "4") (pinfunction "MOSI_4") (pintype "passive"))
      (node (ref "U1") (pin "15") (pinfunction "PB3_(MOSI/OC2A/PCINT3)_15") (pintype "bidirectional"))
    )
    (net (code "24") (name "/1D12{slash}MISO") (class "Default")
      (node (ref "J11") (pin "6") (pinfunction "6_6") (pintype "passive"))
      (node (ref "J13") (pin "1") (pinfunction "MISO_1") (pintype "passive"))
      (node (ref "U1") (pin "16") (pinfunction "PB4_(MISO/PCINT4)_16") (pintype "bidirectional"))
    )
    (net (code "25") (name "/1D13{slash}SCK") (class "Default")
      (node (ref "J11") (pin "5") (pinfunction "5_5") (pintype "passive"))
      (node (ref "J13") (pin "3") (pinfunction "SCK_3") (pintype "passive"))
      (node (ref "R12") (pin "1") (pinfunction "1_1") (pintype "passive"))
      (node (ref "U1") (pin "17") (pinfunction "PB5_(SCK/PCINT5)_17") (pintype "bidirectional"))
    )
    (net (code "26") (name "/2A0") (class "Default")
      (node (ref "J17") (pin "1") (pinfunction "1_1") (pintype "passive"))
      (node (ref "J7") (pin "4") (pinfunction "4_4") (pintype "passive"))
      (node (ref "U2") (pin "23") (pinfunction "_PC0_(ADC0/PCINT8)_23") (pintype "bidirectional"))
    )
    (net (code "27") (name "/2A1") (class "Default")
      (node (ref "J17") (pin "2") (pinfunction "2_2") (pintype "passive"))
      (node (ref "J7") (pin "5") (pinfunction "5_5") (pintype "passive"))
      (node (ref "U2") (pin "24") (pinfunction "_PC1_(ADC1/PCINT9)_24") (pintype "bidirectional"))
    )
    (net (code "28") (name "/2A2") (class "Default")
      (node (ref "J17") (pin "3") (pinfunction "3_3") (pintype "passive"))
      (node (ref "J8") (pin "4") (pinfunction "4_4") (pintype "passive"))
      (node (ref "U2") (pin "25") (pinfunction "_PC2_(ADC2/PCINT10)_25") (pintype "bidirectional"))
    )
    (net (code "29") (name "/2A3") (class "Default")
      (node (ref "J17") (pin "4") (pinfunction "4_4") (pintype "passive"))
      (node (ref "J8") (pin "5") (pinfunction "5_5") (pintype "passive"))
      (node (ref "U2") (pin "26") (pinfunction "_PC3_(ADC3/PCINT11)_26") (pintype "bidirectional"))
    )
    (net (code "30") (name "/2A4") (class "Default")
      (node (ref "J17") (pin "5") (pinfunction "5_5") (pintype "passive"))
      (node (ref "U2") (pin "27") (pinfunction "_PC4_(ADC4/SDA/PCINT12)_27") (pintype "bidirectional"))
    )
    (net (code "31") (name "/2A5") (class "Default")
      (node (ref "J17") (pin "6") (pinfunction "6_6") (pintype "passive"))
      (node (ref "U2") (pin "28") (pinfunction "PC5_(ADC5/SCL/PCINT13)_28") (pintype "bidirectional"))
    )
    (net (code "32") (name "/2A6") (class "Default")
      (node (ref "J16") (pin "2") (pinfunction "2_2") (pintype "passive"))
      (node (ref "U2") (pin "19") (pinfunction "ADC6_19") (pintype "bidirectional"))
    )
    (net (code "33") (name "/2A7") (class "Default")
      (node (ref "J16") (pin "1") (pinfunction "1_1") (pintype "passive"))
      (node (ref "U2") (pin "22") (pinfunction "ADC7_22") (pintype "bidirectional"))
    )
    (net (code "34") (name "/2D0{slash}RXD2") (class "Default")
      (node (ref "D13") (pin "1") (pinfunction "1_1") (pintype "passive"))
      (node (ref "J18") (pin "1") (pinfunction "1_1") (pintype "passive"))
      (node (ref "J23") (pin "2") (pinfunction "2_2") (pintype "passive"))
      (node (ref "U2") (pin "30") (pinfunction "PD0(PCINT16/RXD)_30") (pintype "bidirectional"))
      (node (ref "U4") (pin "2") (pinfunction "TXD_2") (pintype "bidirectional"))
    )
    (net (code "35") (name "/2D1{slash}TXD2") (class "Default")
      (node (ref "D13") (pin "2") (pinfunction "2_2") (pintype "passive"))
      (node (ref "J18") (pin "2") (pinfunction "2_2") (pintype "passive"))
      (node (ref "J23") (pin "3") (pinfunction "3_3") (pintype "passive"))
      (node (ref "U2") (pin "31") (pinfunction "PD1(PCINT17/TXD)_31") (pintype "bidirectional"))
      (node (ref "U4") (pin "3") (pinfunction "RXD_3") (pintype "bidirectional"))
    )
    (net (code "36") (name "/2D2{slash}INT2") (class "Default")
      (node (ref "J18") (pin "3") (pinfunction "3_3") (pintype "passive"))
      (node (ref "J2") (pin "2") (pinfunction "D-_2") (pintype "bidirectional"))
      (node (ref "U2") (pin "32") (pinfunction "PD2__(PCINT18/INT0)_32") (pintype "bidirectional"))
    )
    (net (code "37") (name "/2D3{slash}INT3") (class "Default")
      (node (ref "J18") (pin "4") (pinfunction "4_4") (pintype "passive"))
      (node (ref "J2") (pin "3") (pinfunction "D+_3") (pintype "bidirectional"))
      (node (ref "U2") (pin "1") (pinfunction "PD3(PCINT19/OC2B/INT1)_1") (pintype "bidirectional"))
    )
    (net (code "38") (name "/2D4") (class "Default")
      (node (ref "J18") (pin "5") (pinfunction "5_5") (pintype "passive"))
      (node (ref "U2") (pin "2") (pinfunction "PD4(PCINT20/XCK/T0)_2") (pintype "bidirectional"))
    )
    (net (code "39") (name "/2D5{slash}pwm2") (class "Default")
      (node (ref "J18") (pin "6") (pinfunction "6_6") (pintype "passive"))
      (node (ref "J22") (pin "2") (pinfunction "2_2") (pintype "passive"))
      (node (ref "J8") (pin "2") (pinfunction "2_2") (pintype "passive"))
      (node (ref "R10") (pin "1") (pinfunction "1_1") (pintype "passive"))
      (node (ref "U2") (pin "9") (pinfunction "PD5(PCINT21/OC0B/T1)_9") (pintype "bidirectional"))
    )
    (net (code "40") (name "/2D6{slash}pwm3") (class "Default")
      (node (ref "J18") (pin "7") (pinfunction "7_7") (pintype "passive"))
      (node (ref "J22") (pin "4") (pinfunction "4_4") (pintype "passive"))
      (node (ref "J8") (pin "3") (pinfunction "3_3") (pintype "passive"))
      (node (ref "R11") (pin "1") (pinfunction "1_1") (pintype "passive"))
      (node (ref "U2") (pin "10") (pinfunction "PD6_(PCINT22/OC0A/AIN0)_10") (pintype "bidirectional"))
    )
    (net (code "41") (name "/2D7") (class "Default")
      (node (ref "J18") (pin "8") (pinfunction "8_8") (pintype "passive"))
      (node (ref "U2") (pin "11") (pinfunction "PD7(PCINT23/AIN1)_11") (pintype "bidirectional"))
    )
    (net (code "42") (name "/2D8") (class "Default")
      (node (ref "J16") (pin "10") (pinfunction "10_10") (pintype "passive"))
      (node (ref "U2") (pin "12") (pinfunction "PB0_(PCINT0/CLKO/ICP1)_12") (pintype "bidirectional"))
    )
    (net (code "43") (name "/2D9{slash}pwm0") (class "Default")
      (node (ref "J16") (pin "9") (pinfunction "9_9") (pintype "passive"))
      (node (ref "J22") (pin "6") (pinfunction "6_6") (pintype "passive"))
      (node (ref "J7") (pin "2") (pinfunction "2_2") (pintype "passive"))
      (node (ref "R7") (pin "1") (pinfunction "1_1") (pintype "passive"))
      (node (ref "U2") (pin "13") (pinfunction "PB1_(OC1A/PCINT1)_13") (pintype "bidirectional"))
    )
    (net (code "44") (name "/2D10{slash}pwm1") (class "Default")
      (node (ref "J16") (pin "8") (pinfunction "8_8") (pintype "passive"))
      (node (ref "J22") (pin "8") (pinfunction "8_8") (pintype "passive"))
      (node (ref "J7") (pin "3") (pinfunction "3_3") (pintype "passive"))
      (node (ref "R8") (pin "1") (pinfunction "1_1") (pintype "passive"))
      (node (ref "U2") (pin "14") (pinfunction "PB2_(SS/OC1B/PCINT2)_14") (pintype "bidirectional"))
    )
    (net (code "45") (name "/2D11{slash}MOSI") (class "Default")
      (node (ref "J14") (pin "4") (pinfunction "MOSI_4") (pintype "passive"))
      (node (ref "J16") (pin "5") (pinfunction "5_5") (pintype "passive"))
      (node (ref "U2") (pin "15") (pinfunction "PB3_(MOSI/OC2A/PCINT3)_15") (pintype "bidirectional"))
    )
    (net (code "46") (name "/2D12{slash}MISO") (class "Default")
      (node (ref "J14") (pin "1") (pinfunction "MISO_1") (pintype "passive"))
      (node (ref "J16") (pin "6") (pinfunction "6_6") (pintype "passive"))
      (node (ref "U2") (pin "16") (pinfunction "PB4_(MISO/PCINT4)_16") (pintype "bidirectional"))
    )
    (net (code "47") (name "/2D13{slash}SCK") (class "Default")
      (node (ref "J14") (pin "3") (pinfunction "SCK_3") (pintype "passive"))
      (node (ref "J16") (pin "7") (pinfunction "7_7") (pintype "passive"))
      (node (ref "R13") (pin "1") (pinfunction "1_1") (pintype "passive"))
      (node (ref "U2") (pin "17") (pinfunction "PB5_(SCK/PCINT5)_17") (pintype "bidirectional"))
    )
    (net (code "48") (name "/AREF1") (class "Default")
      (node (ref "C11") (pin "1") (pinfunction "1_1") (pintype "passive"))
      (node (ref "J11") (pin "3") (pinfunction "3_3") (pintype "passive"))
      (node (ref "U1") (pin "20") (pinfunction "AREF_20") (pintype "input"))
    )
    (net (code "49") (name "/AREF2") (class "Default")
      (node (ref "C12") (pin "1") (pinfunction "1_1") (pintype "passive"))
      (node (ref "J16") (pin "3") (pinfunction "3_3") (pintype "passive"))
      (node (ref "U2") (pin "20") (pinfunction "AREF_20") (pintype "input"))
    )
    (net (code "50") (name "/D1_N") (class "Default")
      (node (ref "D14") (pin "3") (pinfunction "I/O_2_3") (pintype "passive"))
      (node (ref "J9") (pin "A7") (pinfunction "DN1_A7") (pintype "bidirectional"))
      (node (ref "J9") (pin "B7") (pinfunction "DN2_B7") (pintype "bidirectional"))
    )
    (net (code "51") (name "/D1_P") (class "Default")
      (node (ref "D14") (pin "1") (pinfunction "I/O_1_1") (pintype "passive"))
      (node (ref "J9") (pin "A6") (pinfunction "DP1_A6") (pintype "bidirectional"))
      (node (ref "J9") (pin "B6") (pinfunction "DP2_B6") (pintype "bidirectional"))
    )
    (net (code "52") (name "/D1_out_N") (class "Default")
      (node (ref "D14") (pin "4") (pinfunction "I/O_2_4") (pintype "passive"))
      (node (ref "U3") (pin "6") (pinfunction "UD-_6") (pintype "bidirectional"))
    )
    (net (code "53") (name "/D1_out_P") (class "Default")
      (node (ref "D14") (pin "6") (pinfunction "I/O_1_6") (pintype "passive"))
      (node (ref "U3") (pin "5") (pinfunction "UD+_5") (pintype "bidirectional"))
    )
    (net (code "54") (name "/D2_N") (class "Default")
      (node (ref "D15") (pin "3") (pinfunction "I/O_2_3") (pintype "passive"))
      (node (ref "J10") (pin "A7") (pinfunction "DN1_A7") (pintype "bidirectional"))
      (node (ref "J10") (pin "B7") (pinfunction "DN2_B7") (pintype "bidirectional"))
    )
    (net (code "55") (name "/D2_P") (class "Default")
      (node (ref "D15") (pin "1") (pinfunction "I/O_1_1") (pintype "passive"))
      (node (ref "J10") (pin "A6") (pinfunction "DP1_A6") (pintype "bidirectional"))
      (node (ref "J10") (pin "B6") (pinfunction "DP2_B6") (pintype "bidirectional"))
    )
    (net (code "56") (name "/D2_out_N") (class "Default")
      (node (ref "D15") (pin "4") (pinfunction "I/O_2_4") (pintype "passive"))
      (node (ref "U4") (pin "6") (pinfunction "UD-_6") (pintype "bidirectional"))
    )
    (net (code "57") (name "/D2_out_P") (class "Default")
      (node (ref "D15") (pin "6") (pinfunction "I/O_1_6") (pintype "passive"))
      (node (ref "U4") (pin "5") (pinfunction "UD+_5") (pintype "bidirectional"))
    )
    (net (code "58") (name "/PR1") (class "Default")
      (node (ref "R19") (pin "2") (pinfunction "2_2") (pintype "passive"))
      (node (ref "R20") (pin "2") (pinfunction "2_2") (pintype "passive"))
      (node (ref "U5") (pin "4") (pinfunction "PR1_4") (pintype "passive"))
    )
    (net (code "59") (name "/PR2") (class "Default")
      (node (ref "R22") (pin "2") (pinfunction "2_2") (pintype "passive"))
      (node (ref "R23") (pin "2") (pinfunction "2_2") (pintype "passive"))
      (node (ref "U6") (pin "4") (pinfunction "PR1_4") (pintype "passive"))
    )
    (net (code "60") (name "/reset1") (class "Default")
      (node (ref "C15") (pin "2") (pinfunction "2_2") (pintype "passive"))
      (node (ref "C19") (pin "2") (pinfunction "2_2") (pintype "passive"))
      (node (ref "J13") (pin "5") (pinfunction "RESET_5") (pintype "passive"))
      (node (ref "J6") (pin "2") (pinfunction "2_2") (pintype "passive"))
      (node (ref "R1") (pin "2") (pinfunction "2_2") (pintype "passive"))
      (node (ref "S1") (pin "2") (pinfunction "2_2") (pintype "passive"))
      (node (ref "U1") (pin "29") (pinfunction "PC6/~{RESET}_29") (pintype "bidirectional"))
    )
    (net (code "61") (name "/reset2") (class "Default")
      (node (ref "C18") (pin "2") (pinfunction "2_2") (pintype "passive"))
      (node (ref "C20") (pin "2") (pinfunction "2_2") (pintype "passive"))
      (node (ref "J14") (pin "5") (pinfunction "RESET_5") (pintype "passive"))
      (node (ref "J23") (pin "4") (pinfunction "4_4") (pintype "passive"))
      (node (ref "R2") (pin "2") (pinfunction "2_2") (pintype "passive"))
      (node (ref "S2") (pin "2") (pinfunction "2_2") (pintype "passive"))
      (node (ref "U2") (pin "29") (pinfunction "PC6/~{RESET}_29") (pintype "bidirectional"))
    )
    (net (code "62") (name "GND") (class "Default")
      (node (ref "C1") (pin "1") (pinfunction "1_1") (pintype "passive"))
      (node (ref "C10") (pin "1") (pinfunction "1_1") (pintype "passive"))
      (node (ref "C11") (pin "2") (pinfunction "2_2") (pintype "passive"))
      (node (ref "C12") (pin "2") (pinfunction "2_2") (pintype "passive"))
      (node (ref "C13") (pin "2") (pinfunction "2_2") (pintype "passive"))
      (node (ref "C14") (pin "2") (pinfunction "2_2") (pintype "passive"))
      (node (ref "C16") (pin "2") (pinfunction "2_2") (pintype "passive"))
      (node (ref "C17") (pin "2") (pinfunction "2_2") (pintype "passive"))
      (node (ref "C19") (pin "1") (pinfunction "1_1") (pintype "passive"))
      (node (ref "C2") (pin "1") (pinfunction "1_1") (pintype "passive"))
      (node (ref "C20") (pin "1") (pinfunction "1_1") (pintype "passive"))
      (node (ref "C3") (pin "1") (pinfunction "1_1") (pintype "passive"))
      (node (ref "C4") (pin "1") (pinfunction "1_1") (pintype "passive"))
      (node (ref "C5") (pin "1") (pinfunction "1_1") (pintype "passive"))
      (node (ref "C6") (pin "1") (pinfunction "1_1") (pintype "passive"))
      (node (ref "C7") (pin "1") (pinfunction "1_1") (pintype "passive"))
      (node (ref "C8") (pin "1") (pinfunction "1_1") (pintype "passive"))
      (node (ref "C9") (pin "1") (pinfunction "1_1") (pintype "passive"))
      (node (ref "D1") (pin "2") (pinfunction "2_2") (pintype "passive"))
      (node (ref "D10") (pin "2") (pinfunction "2_2") (pintype "passive"))
      (node (ref "D11") (pin "2") (pinfunction "2_2") (pintype "passive"))
      (node (ref "D12") (pin "3") (pinfunction "3_3") (pintype "passive"))
      (node (ref "D13") (pin "3") (pinfunction "3_3") (pintype "passive"))
      (node (ref "D14") (pin "2") (pinfunction "GND_2") (pintype "passive"))
      (node (ref "D15") (pin "2") (pinfunction "GND_2") (pintype "passive"))
      (node (ref "D16") (pin "2") (pinfunction "2_2") (pintype "passive"))
      (node (ref "D17") (pin "2") (pinfunction "2_2") (pintype "passive"))
      (node (ref "D2") (pin "2") (pinfunction "2_2") (pintype "passive"))
      (node (ref "D3") (pin "2") (pinfunction "2_2") (pintype "passive"))
      (node (ref "D4") (pin "2") (pinfunction "2_2") (pintype "passive"))
      (node (ref "D5") (pin "2") (pinfunction "2_2") (pintype "passive"))
      (node (ref "D6") (pin "2") (pinfunction "2_2") (pintype "passive"))
      (node (ref "D7") (pin "2") (pinfunction "2_2") (pintype "passive"))
      (node (ref "D8") (pin "2") (pinfunction "2_2") (pintype "passive"))
      (node (ref "D9") (pin "2") (pinfunction "2_2") (pintype "passive"))
      (node (ref "J1") (pin "4") (pinfunction "GND_4") (pintype "power_in"))
      (node (ref "J1") (pin "s1") (pinfunction "SHIELD_s1") (pintype "passive"))
      (node (ref "J1") (pin "s2") (pinfunction "SHIELD_s2") (pintype "passive"))
      (node (ref "J10") (pin "A1/B12") (pinfunction "GND_A1/B12") (pintype "power_in"))
      (node (ref "J10") (pin "B1/A12") (pinfunction "GND_B1/A12") (pintype "power_in"))
      (node (ref "J10") (pin "S1") (pinfunction "SHIELD_S1") (pintype "passive"))
      (node (ref "J10") (pin "S2") (pinfunction "SHIELD_S2") (pintype "passive"))
      (node (ref "J10") (pin "S3") (pinfunction "SHIELD_S3") (pintype "passive"))
      (node (ref "J10") (pin "S4") (pinfunction "SHIELD_S4") (pintype "passive"))
      (node (ref "J11") (pin "4") (pinfunction "4_4") (pintype "passive"))
      (node (ref "J13") (pin "6") (pinfunction "GND_6") (pintype "passive"))
      (node (ref "J14") (pin "6") (pinfunction "GND_6") (pintype "passive"))
      (node (ref "J16") (pin "4") (pinfunction "4_4") (pintype "passive"))
      (node (ref "J19") (pin "1") (pinfunction "1_1") (pintype "passive"))
      (node (ref "J19") (pin "3") (pinfunction "3_3") (pintype "passive"))
      (node (ref "J2") (pin "4") (pinfunction "GND_4") (pintype "power_in"))
      (node (ref "J2") (pin "s1") (pinfunction "SHIELD_s1") (pintype "passive"))
      (node (ref "J2") (pin "s2") (pinfunction "SHIELD_s2") (pintype "passive"))
      (node (ref "J21") (pin "3") (pinfunction "3_3") (pintype "passive"))
      (node (ref "J23") (pin "5") (pinfunction "5_5") (pintype "passive"))
      (node (ref "J3") (pin "6") (pinfunction "6_6") (pintype "passive"))
      (node (ref "J4") (pin "6") (pinfunction "6_6") (pintype "passive"))
      (node (ref "J6") (pin "1") (pinfunction "1_1") (pintype "passive"))
      (node (ref "J7") (pin "6") (pinfunction "6_6") (pintype "passive"))
      (node (ref "J8") (pin "6") (pinfunction "6_6") (pintype "passive"))
      (node (ref "J9") (pin "A1/B12") (pinfunction "GND_A1/B12") (pintype "power_in"))
      (node (ref "J9") (pin "B1/A12") (pinfunction "GND_B1/A12") (pintype "power_in"))
      (node (ref "J9") (pin "S1") (pinfunction "SHIELD_S1") (pintype "passive"))
      (node (ref "J9") (pin "S2") (pinfunction "SHIELD_S2") (pintype "passive"))
      (node (ref "J9") (pin "S3") (pinfunction "SHIELD_S3") (pintype "passive"))
      (node (ref "J9") (pin "S4") (pinfunction "SHIELD_S4") (pintype "passive"))
      (node (ref "R14") (pin "1") (pinfunction "1_1") (pintype "passive"))
      (node (ref "R15") (pin "2") (pinfunction "2_2") (pintype "passive"))
      (node (ref "R16") (pin "1") (pinfunction "1_1") (pintype "passive"))
      (node (ref "R17") (pin "2") (pinfunction "2_2") (pintype "passive"))
      (node (ref "R20") (pin "1") (pinfunction "1_1") (pintype "passive"))
      (node (ref "R23") (pin "1") (pinfunction "1_1") (pintype "passive"))
      (node (ref "S1") (pin "1") (pinfunction "1_1") (pintype "passive"))
      (node (ref "S2") (pin "1") (pinfunction "1_1") (pintype "passive"))
      (node (ref "U1") (pin "21") (pinfunction "GND_21") (pintype "power_in"))
      (node (ref "U1") (pin "3") (pinfunction "GND_3") (pintype "power_in"))
      (node (ref "U1") (pin "5") (pinfunction "GND_5") (pintype "power_in"))
      (node (ref "U2") (pin "21") (pinfunction "GND_21") (pintype "power_in"))
      (node (ref "U2") (pin "3") (pinfunction "GND_3") (pintype "power_in"))
      (node (ref "U2") (pin "5") (pinfunction "GND_5") (pintype "power_in"))
      (node (ref "U3") (pin "1") (pinfunction "GND_1") (pintype "power_in"))
      (node (ref "U4") (pin "1") (pinfunction "GND_1") (pintype "power_in"))
      (node (ref "U5") (pin "1") (pinfunction "GND_1") (pintype "passive"))
      (node (ref "U6") (pin "1") (pinfunction "GND_1") (pintype "passive"))
    )
    (net (code "63") (name "Net-(D1-Pad1)") (class "Default")
      (node (ref "D1") (pin "1") (pinfunction "1_1") (pintype "passive"))
      (node (ref "R3") (pin "2") (pinfunction "2_2") (pintype "passive"))
    )
    (net (code "64") (name "Net-(D2-Pad1)") (class "Default")
      (node (ref "D2") (pin "1") (pinfunction "1_1") (pintype "passive"))
      (node (ref "R4") (pin "2") (pinfunction "2_2") (pintype "passive"))
    )
    (net (code "65") (name "Net-(D3-Pad1)") (class "Default")
      (node (ref "D3") (pin "1") (pinfunction "1_1") (pintype "passive"))
      (node (ref "R5") (pin "2") (pinfunction "2_2") (pintype "passive"))
    )
    (net (code "66") (name "Net-(D4-Pad1)") (class "Default")
      (node (ref "D4") (pin "1") (pinfunction "1_1") (pintype "passive"))
      (node (ref "R6") (pin "2") (pinfunction "2_2") (pintype "passive"))
    )
    (net (code "67") (name "Net-(D5-Pad1)") (class "Default")
      (node (ref "D5") (pin "1") (pinfunction "1_1") (pintype "passive"))
      (node (ref "R7") (pin "2") (pinfunction "2_2") (pintype "passive"))
    )
    (net (code "68") (name "Net-(D6-Pad1)") (class "Default")
      (node (ref "D6") (pin "1") (pinfunction "1_1") (pintype "passive"))
      (node (ref "R8") (pin "2") (pinfunction "2_2") (pintype "passive"))
    )
    (net (code "69") (name "Net-(D7-Pad1)") (class "Default")
      (node (ref "D7") (pin "1") (pinfunction "1_1") (pintype "passive"))
      (node (ref "R9") (pin "2") (pinfunction "2_2") (pintype "passive"))
    )
    (net (code "70") (name "Net-(D8-Pad1)") (class "Default")
      (node (ref "D8") (pin "1") (pinfunction "1_1") (pintype "passive"))
      (node (ref "R10") (pin "2") (pinfunction "2_2") (pintype "passive"))
    )
    (net (code "71") (name "Net-(D9-Pad1)") (class "Default")
      (node (ref "D9") (pin "1") (pinfunction "1_1") (pintype "passive"))
      (node (ref "R11") (pin "2") (pinfunction "2_2") (pintype "passive"))
    )
    (net (code "72") (name "Net-(D10-Pad1)") (class "Default")
      (node (ref "D10") (pin "1") (pinfunction "1_1") (pintype "passive"))
      (node (ref "R12") (pin "2") (pinfunction "2_2") (pintype "passive"))
    )
    (net (code "73") (name "Net-(D11-Pad1)") (class "Default")
      (node (ref "D11") (pin "1") (pinfunction "1_1") (pintype "passive"))
      (node (ref "R13") (pin "2") (pinfunction "2_2") (pintype "passive"))
    )
    (net (code "74") (name "Net-(D16-Pad1)") (class "Default")
      (node (ref "D16") (pin "1") (pinfunction "1_1") (pintype "passive"))
      (node (ref "R24") (pin "2") (pinfunction "2_2") (pintype "passive"))
    )
    (net (code "75") (name "Net-(D17-Pad1)") (class "Default")
      (node (ref "D17") (pin "1") (pinfunction "1_1") (pintype "passive"))
      (node (ref "R25") (pin "2") (pinfunction "2_2") (pintype "passive"))
    )
    (net (code "76") (name "Net-(J9-CC1)") (class "Default")
      (node (ref "J9") (pin "A5") (pinfunction "CC1_A5") (pintype "bidirectional"))
      (node (ref "R14") (pin "2") (pinfunction "2_2") (pintype "passive"))
    )
    (net (code "77") (name "Net-(J9-CC2)") (class "Default")
      (node (ref "J9") (pin "B5") (pinfunction "CC2_B5") (pintype "bidirectional"))
      (node (ref "R15") (pin "1") (pinfunction "1_1") (pintype "passive"))
    )
    (net (code "78") (name "Net-(J10-CC1)") (class "Default")
      (node (ref "J10") (pin "A5") (pinfunction "CC1_A5") (pintype "bidirectional"))
      (node (ref "R16") (pin "2") (pinfunction "2_2") (pintype "passive"))
    )
    (net (code "79") (name "Net-(J10-CC2)") (class "Default")
      (node (ref "J10") (pin "B5") (pinfunction "CC2_B5") (pintype "bidirectional"))
      (node (ref "R17") (pin "1") (pinfunction "1_1") (pintype "passive"))
    )
    (net (code "80") (name "Net-(U1-PB6(PCINT6{slash}XTAL1{slash}TOSC1))") (class "Default")
      (node (ref "C1") (pin "2") (pinfunction "2_2") (pintype "passive"))
      (node (ref "U1") (pin "7") (pinfunction "PB6(PCINT6/XTAL1/TOSC1)_7") (pintype "bidirectional"))
      (node (ref "Y1") (pin "2") (pinfunction "2_2") (pintype "passive"))
    )
    (net (code "81") (name "Net-(U1-PB7(PCINT7{slash}XTAL2{slash}TOSC2))") (class "Default")
      (node (ref "C2") (pin "2") (pinfunction "2_2") (pintype "passive"))
      (node (ref "U1") (pin "8") (pinfunction "PB7(PCINT7/XTAL2/TOSC2)_8") (pintype "bidirectional"))
      (node (ref "Y1") (pin "1") (pinfunction "1_1") (pintype "passive"))
    )
    (net (code "82") (name "Net-(U2-PB6(PCINT6{slash}XTAL1{slash}TOSC1))") (class "Default")
      (node (ref "C3") (pin "2") (pinfunction "2_2") (pintype "passive"))
      (node (ref "U2") (pin "7") (pinfunction "PB6(PCINT6/XTAL1/TOSC1)_7") (pintype "bidirectional"))
      (node (ref "Y2") (pin "2") (pinfunction "2_2") (pintype "passive"))
    )
    (net (code "83") (name "Net-(U2-PB7(PCINT7{slash}XTAL2{slash}TOSC2))") (class "Default")
      (node (ref "C4") (pin "2") (pinfunction "2_2") (pintype "passive"))
      (node (ref "U2") (pin "8") (pinfunction "PB7(PCINT7/XTAL2/TOSC2)_8") (pintype "bidirectional"))
      (node (ref "Y2") (pin "1") (pinfunction "1_1") (pintype "passive"))
    )
    (net (code "84") (name "Net-(U3-V3)") (class "Default")
      (node (ref "C13") (pin "1") (pinfunction "1_1") (pintype "passive"))
      (node (ref "U3") (pin "4") (pinfunction "V3_4") (pintype "power_in"))
    )
    (net (code "85") (name "Net-(U3-~{DTR})") (class "Default")
      (node (ref "C15") (pin "1") (pinfunction "1_1") (pintype "passive"))
      (node (ref "U3") (pin "13") (pinfunction "~{DTR}_13") (pintype "output"))
    )
    (net (code "86") (name "Net-(U4-V3)") (class "Default")
      (node (ref "C16") (pin "1") (pinfunction "1_1") (pintype "passive"))
      (node (ref "U4") (pin "4") (pinfunction "V3_4") (pintype "power_in"))
    )
    (net (code "87") (name "Net-(U4-~{DTR})") (class "Default")
      (node (ref "C18") (pin "1") (pinfunction "1_1") (pintype "passive"))
      (node (ref "U4") (pin "13") (pinfunction "~{DTR}_13") (pintype "output"))
    )
    (net (code "88") (name "Net-(U5-ST)") (class "Default")
      (node (ref "R18") (pin "1") (pinfunction "1_1") (pintype "passive"))
      (node (ref "U5") (pin "8") (pinfunction "ST_8") (pintype "passive"))
    )
    (net (code "89") (name "Net-(U6-ST)") (class "Default")
      (node (ref "R21") (pin "1") (pinfunction "1_1") (pintype "passive"))
      (node (ref "U6") (pin "8") (pinfunction "ST_8") (pintype "passive"))
    )
    (net (code "90") (name "Vbus1") (class "Default")
      (node (ref "C14") (pin "1") (pinfunction "1_1") (pintype "passive"))
      (node (ref "D14") (pin "5") (pinfunction "Vbus_5") (pintype "passive"))
      (node (ref "J20") (pin "3") (pinfunction "3_3") (pintype "passive"))
      (node (ref "J6") (pin "5") (pinfunction "5_5") (pintype "passive"))
      (node (ref "J9") (pin "A4/B9") (pinfunction "VBUS_A4/B9") (pintype "power_in"))
      (node (ref "J9") (pin "B4/A9") (pinfunction "VBUS_B4/A9") (pintype "power_in"))
      (node (ref "R18") (pin "2") (pinfunction "2_2") (pintype "passive"))
      (node (ref "R19") (pin "1") (pinfunction "1_1") (pintype "passive"))
      (node (ref "U5") (pin "3") (pinfunction "Vin1_3") (pintype "passive"))
      (node (ref "U5") (pin "5") (pinfunction "MODE_5") (pintype "passive"))
    )
    (net (code "91") (name "Vbus2") (class "Default")
      (node (ref "C17") (pin "1") (pinfunction "1_1") (pintype "passive"))
      (node (ref "D15") (pin "5") (pinfunction "Vbus_5") (pintype "passive"))
      (node (ref "J10") (pin "A4/B9") (pinfunction "VBUS_A4/B9") (pintype "power_in"))
      (node (ref "J10") (pin "B4/A9") (pinfunction "VBUS_B4/A9") (pintype "power_in"))
      (node (ref "J20") (pin "1") (pinfunction "1_1") (pintype "passive"))
      (node (ref "J23") (pin "1") (pinfunction "1_1") (pintype "passive"))
      (node (ref "U5") (pin "6") (pinfunction "Vin2_6") (pintype "passive"))
    )
    (net (code "92") (name "Vin") (class "Default")
      (node (ref "J19") (pin "2") (pinfunction "2_2") (pintype "passive"))
      (node (ref "J20") (pin "5") (pinfunction "5_5") (pintype "passive"))
      (node (ref "R21") (pin "2") (pinfunction "2_2") (pintype "passive"))
      (node (ref "R22") (pin "1") (pinfunction "1_1") (pintype "passive"))
      (node (ref "R24") (pin "1") (pinfunction "1_1") (pintype "passive"))
      (node (ref "U6") (pin "3") (pinfunction "Vin1_3") (pintype "passive"))
      (node (ref "U6") (pin "5") (pinfunction "MODE_5") (pintype "passive"))
    )
    (net (code "93") (name "Vout") (class "Default")
      (node (ref "R25") (pin "1") (pinfunction "1_1") (pintype "passive"))
      (node (ref "U5") (pin "2") (pinfunction "Vout_2") (pintype "passive"))
      (node (ref "U5") (pin "7") (pinfunction "Vout_7") (pintype "passive"))
      (node (ref "U6") (pin "6") (pinfunction "Vin2_6") (pintype "passive"))
    )
    (net (code "94") (name "unconnected-(J9-SBU1-PadA8)") (class "Default")
      (node (ref "J9") (pin "A8") (pinfunction "SBU1_A8") (pintype "bidirectional+no_connect"))
    )
    (net (code "95") (name "unconnected-(J9-SBU2-PadB8)") (class "Default")
      (node (ref "J9") (pin "B8") (pinfunction "SBU2_B8") (pintype "bidirectional+no_connect"))
    )
    (net (code "96") (name "unconnected-(J10-SBU1-PadA8)") (class "Default")
      (node (ref "J10") (pin "A8") (pinfunction "SBU1_A8") (pintype "bidirectional+no_connect"))
    )
    (net (code "97") (name "unconnected-(J10-SBU2-PadB8)") (class "Default")
      (node (ref "J10") (pin "B8") (pinfunction "SBU2_B8") (pintype "bidirectional+no_connect"))
    )
    (net (code "98") (name "unconnected-(J21-Pad1)") (class "Default")
      (node (ref "J21") (pin "1") (pinfunction "1_1") (pintype "passive+no_connect"))
    )
    (net (code "99") (name "unconnected-(J21-Pad6)") (class "Default")
      (node (ref "J21") (pin "6") (pinfunction "6_6") (pintype "passive+no_connect"))
    )
    (net (code "100") (name "unconnected-(U3-NC.-Pad7)") (class "Default")
      (node (ref "U3") (pin "7") (pinfunction "NC._7") (pintype "passive+no_connect"))
    )
    (net (code "101") (name "unconnected-(U3-R232-Pad15)") (class "Default")
      (node (ref "U3") (pin "15") (pinfunction "R232_15") (pintype "passive+no_connect"))
    )
    (net (code "102") (name "unconnected-(U3-~{CTS}-Pad9)") (class "Default")
      (node (ref "U3") (pin "9") (pinfunction "~{CTS}_9") (pintype "passive+no_connect"))
    )
    (net (code "103") (name "unconnected-(U3-~{DCD}-Pad12)") (class "Default")
      (node (ref "U3") (pin "12") (pinfunction "~{DCD}_12") (pintype "passive+no_connect"))
    )
    (net (code "104") (name "unconnected-(U3-~{DSR}-Pad10)") (class "Default")
      (node (ref "U3") (pin "10") (pinfunction "~{DSR}_10") (pintype "passive+no_connect"))
    )
    (net (code "105") (name "unconnected-(U3-~{OUT}-Pad8)") (class "Default")
      (node (ref "U3") (pin "8") (pinfunction "~{OUT}_8") (pintype "passive+no_connect"))
    )
    (net (code "106") (name "unconnected-(U3-~{RI}-Pad11)") (class "Default")
      (node (ref "U3") (pin "11") (pinfunction "~{RI}_11") (pintype "passive+no_connect"))
    )
    (net (code "107") (name "unconnected-(U3-~{RTS}-Pad14)") (class "Default")
      (node (ref "U3") (pin "14") (pinfunction "~{RTS}_14") (pintype "passive+no_connect"))
    )
    (net (code "108") (name "unconnected-(U4-NC.-Pad7)") (class "Default")
      (node (ref "U4") (pin "7") (pinfunction "NC._7") (pintype "passive+no_connect"))
    )
    (net (code "109") (name "unconnected-(U4-R232-Pad15)") (class "Default")
      (node (ref "U4") (pin "15") (pinfunction "R232_15") (pintype "passive+no_connect"))
    )
    (net (code "110") (name "unconnected-(U4-~{CTS}-Pad9)") (class "Default")
      (node (ref "U4") (pin "9") (pinfunction "~{CTS}_9") (pintype "passive+no_connect"))
    )
    (net (code "111") (name "unconnected-(U4-~{DCD}-Pad12)") (class "Default")
      (node (ref "U4") (pin "12") (pinfunction "~{DCD}_12") (pintype "passive+no_connect"))
    )
    (net (code "112") (name "unconnected-(U4-~{DSR}-Pad10)") (class "Default")
      (node (ref "U4") (pin "10") (pinfunction "~{DSR}_10") (pintype "passive+no_connect"))
    )
    (net (code "113") (name "unconnected-(U4-~{OUT}-Pad8)") (class "Default")
      (node (ref "U4") (pin "8") (pinfunction "~{OUT}_8") (pintype "passive+no_connect"))
    )
    (net (code "114") (name "unconnected-(U4-~{RI}-Pad11)") (class "Default")
      (node (ref "U4") (pin "11") (pinfunction "~{RI}_11") (pintype "passive+no_connect"))
    )
    (net (code "115") (name "unconnected-(U4-~{RTS}-Pad14)") (class "Default")
      (node (ref "U4") (pin "14") (pinfunction "~{RTS}_14") (pintype "passive+no_connect"))
    )
  )
)
